# DecoderCircuit_M2.net
KiCad netlist of a schematic drawn in Altium Designer
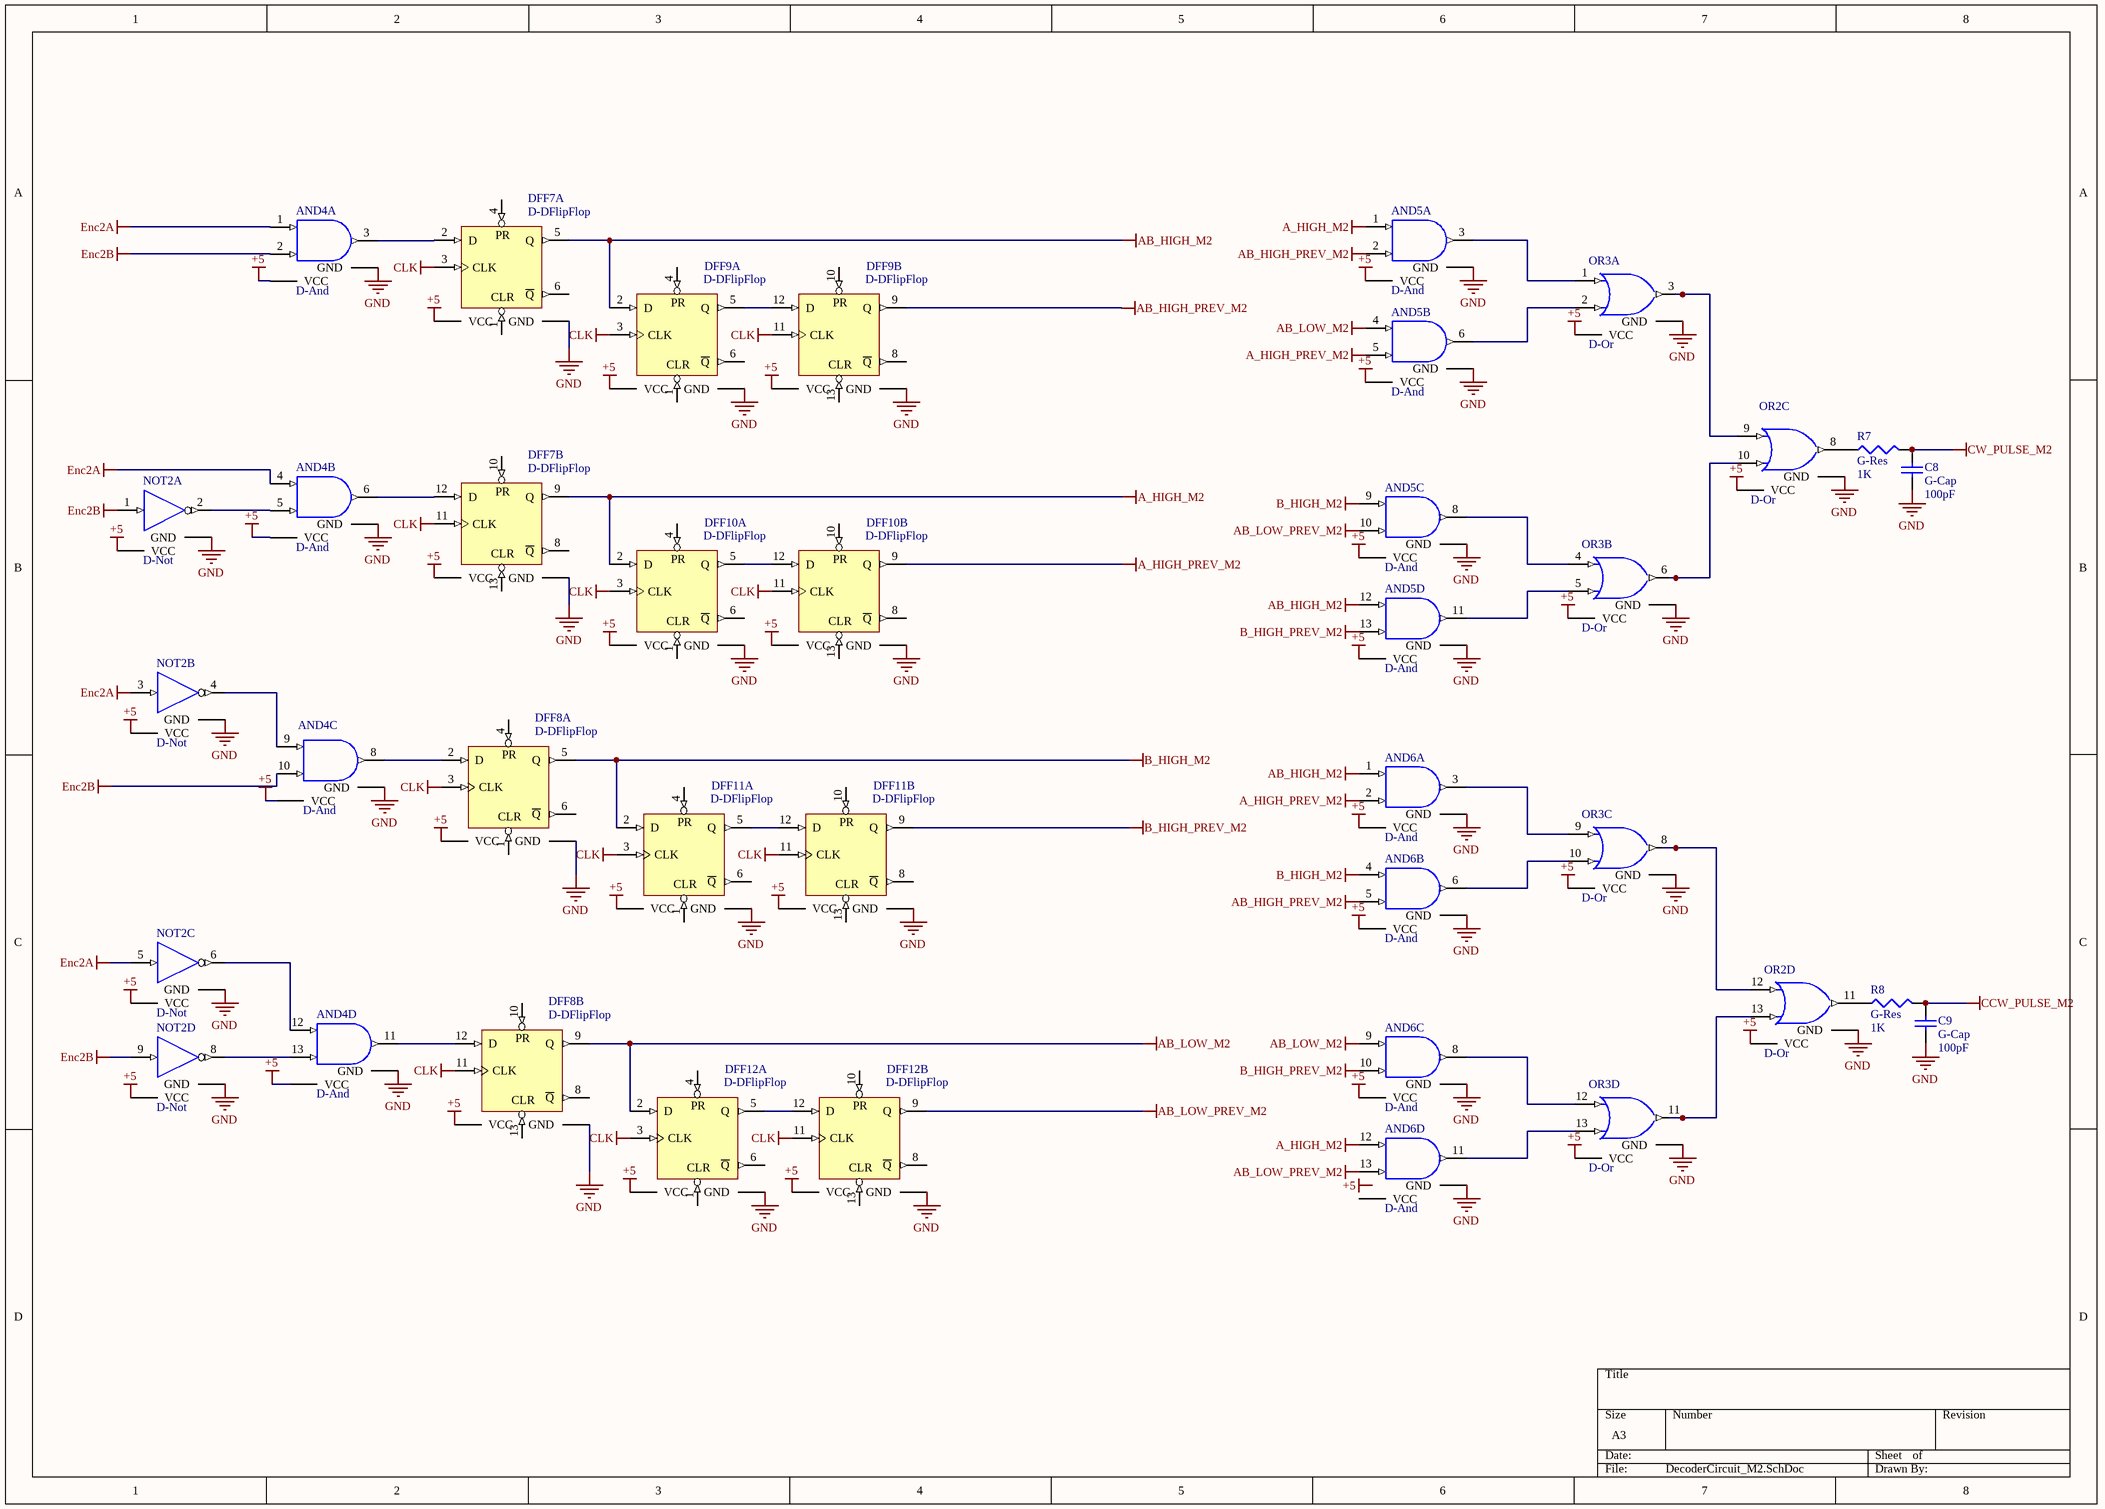
[diagram p0: DecoderCircuit_M2.SchDoc]

(export (version "E")
  (design (tool "Eeschema 10.0.6"))
  (components
    (comp (ref "AND4")
      (value "D-And")
      (footprint "DIP14_LGE1.0")
      (description "Quad 2-input AND gate")
      (fields (field (name "PUBLISHER") "Altium Limited"))
      (libsource (lib "PartsDatabaseV16.1") (part "D-And"))
    )
    (comp (ref "AND5")
      (value "D-And")
      (footprint "DIP14_LGE1.0")
      (description "Quad 2-input AND gate")
      (fields (field (name "PUBLISHER") "Altium Limited"))
      (libsource (lib "PartsDatabaseV16.1") (part "D-And"))
    )
    (comp (ref "AND6")
      (value "D-And")
      (footprint "DIP14_LGE1.0")
      (description "Quad 2-input AND gate")
      (fields (field (name "PUBLISHER") "Altium Limited"))
      (libsource (lib "PartsDatabaseV16.1") (part "D-And"))
    )
    (comp (ref "C8")
      (value "G-Cap")
      (footprint "Cap2.54mm_LGE1.0")
      (description "Capacitor (specify value)")
      (fields (field (name "ALTIUM_VALUE") "100pF") (field (name "PUBLISHER") "Altium Limited"))
      (libsource (lib "PartsDatabaseV16.1") (part "G-Cap"))
    )
    (comp (ref "C9")
      (value "G-Cap")
      (footprint "Cap2.54mm_LGE1.0")
      (description "Capacitor (specify value)")
      (fields (field (name "ALTIUM_VALUE") "100pF") (field (name "PUBLISHER") "Altium Limited"))
      (libsource (lib "PartsDatabaseV16.1") (part "G-Cap"))
    )
    (comp (ref "DFF7")
      (value "D-DFlipFlop")
      (footprint "DIP14_LGE1.0")
      (description "Dual D flip-flop")
      (fields (field (name "PUBLISHER") "Altium Limited"))
      (libsource (lib "PartsDatabaseV16.1") (part "D-DFlipFlop"))
    )
    (comp (ref "DFF8")
      (value "D-DFlipFlop")
      (footprint "DIP14_LGE1.0")
      (description "Dual D flip-flop")
      (fields (field (name "PUBLISHER") "Altium Limited"))
      (libsource (lib "PartsDatabaseV16.1") (part "D-DFlipFlop"))
    )
    (comp (ref "DFF9")
      (value "D-DFlipFlop")
      (footprint "DIP14_LGE1.0")
      (description "Dual D flip-flop")
      (fields (field (name "PUBLISHER") "Altium Limited"))
      (libsource (lib "PartsDatabaseV16.1") (part "D-DFlipFlop"))
    )
    (comp (ref "DFF10")
      (value "D-DFlipFlop")
      (footprint "DIP14_LGE1.0")
      (description "Dual D flip-flop")
      (fields (field (name "PUBLISHER") "Altium Limited"))
      (libsource (lib "PartsDatabaseV16.1") (part "D-DFlipFlop"))
    )
    (comp (ref "DFF11")
      (value "D-DFlipFlop")
      (footprint "DIP14_LGE1.0")
      (description "Dual D flip-flop")
      (fields (field (name "PUBLISHER") "Altium Limited"))
      (libsource (lib "PartsDatabaseV16.1") (part "D-DFlipFlop"))
    )
    (comp (ref "DFF12")
      (value "D-DFlipFlop")
      (footprint "DIP14_LGE1.0")
      (description "Dual D flip-flop")
      (fields (field (name "PUBLISHER") "Altium Limited"))
      (libsource (lib "PartsDatabaseV16.1") (part "D-DFlipFlop"))
    )
    (comp (ref "NOT2")
      (value "D-Not")
      (footprint "DIP14_LGE1.0")
      (description "Hex NOT gate (inverter)")
      (fields (field (name "PUBLISHER") "Altium Limited"))
      (libsource (lib "PartsDatabaseV16.1") (part "D-Not"))
    )
    (comp (ref "OR2")
      (value "D-Or")
      (footprint "DIP14_LGE1.0")
      (description "Quad 2-input OR gate")
      (fields (field (name "PUBLISHER") "Altium Limited"))
      (libsource (lib "PartsDatabaseV16.1") (part "D-Or"))
    )
    (comp (ref "OR3")
      (value "D-Or")
      (footprint "DIP14_LGE1.0")
      (description "Quad 2-input OR gate")
      (fields (field (name "PUBLISHER") "Altium Limited"))
      (libsource (lib "PartsDatabaseV16.1") (part "D-Or"))
    )
    (comp (ref "R7")
      (value "G-Res")
      (footprint "Res10mm_LGE1.0")
      (description "Resistor (specify value)")
      (fields (field (name "ALTIUM_VALUE") "1K") (field (name "PUBLISHER") "Altium Limited"))
      (libsource (lib "PartsDatabaseV16.1") (part "G-Res"))
    )
    (comp (ref "R8")
      (value "G-Res")
      (footprint "Res10mm_LGE1.0")
      (description "Resistor (specify value)")
      (fields (field (name "ALTIUM_VALUE") "1K") (field (name "PUBLISHER") "Altium Limited"))
      (libsource (lib "PartsDatabaseV16.1") (part "G-Res"))
    )
  )
  (nets
    (net (code "1") (name "+5") (class "Default")
      (node (ref "AND4") (pin "14") (pinfunction "VCC_14") (pintype "power_in"))
      (node (ref "AND5") (pin "14") (pinfunction "VCC_14") (pintype "power_in"))
      (node (ref "AND6") (pin "14") (pinfunction "VCC_14") (pintype "power_in"))
      (node (ref "DFF10") (pin "14") (pinfunction "VCC_14") (pintype "power_in"))
      (node (ref "DFF11") (pin "14") (pinfunction "VCC_14") (pintype "power_in"))
      (node (ref "DFF12") (pin "14") (pinfunction "VCC_14") (pintype "power_in"))
      (node (ref "DFF7") (pin "14") (pinfunction "VCC_14") (pintype "power_in"))
      (node (ref "DFF8") (pin "14") (pinfunction "VCC_14") (pintype "power_in"))
      (node (ref "DFF9") (pin "14") (pinfunction "VCC_14") (pintype "power_in"))
      (node (ref "NOT2") (pin "14") (pinfunction "VCC_14") (pintype "power_in"))
      (node (ref "OR2") (pin "14") (pinfunction "VCC_14") (pintype "power_in"))
      (node (ref "OR3") (pin "14") (pinfunction "VCC_14") (pintype "power_in"))
    )
    (net (code "2") (name "AB_HIGH_M2") (class "Default")
      (node (ref "AND5") (pin "12") (pinfunction "A_12") (pintype "input"))
      (node (ref "AND6") (pin "1") (pinfunction "A_1") (pintype "input"))
      (node (ref "DFF7") (pin "5") (pinfunction "Q_5") (pintype "output"))
      (node (ref "DFF9") (pin "2") (pinfunction "D_2") (pintype "input"))
    )
    (net (code "3") (name "AB_HIGH_PREV_M2") (class "Default")
      (node (ref "AND5") (pin "2") (pinfunction "B_2") (pintype "input"))
      (node (ref "AND6") (pin "5") (pinfunction "B_5") (pintype "input"))
      (node (ref "DFF9") (pin "9") (pinfunction "Q_9") (pintype "output"))
    )
    (net (code "4") (name "AB_LOW_M2") (class "Default")
      (node (ref "AND5") (pin "4") (pinfunction "A_4") (pintype "input"))
      (node (ref "AND6") (pin "9") (pinfunction "A_9") (pintype "input"))
      (node (ref "DFF12") (pin "2") (pinfunction "D_2") (pintype "input"))
      (node (ref "DFF8") (pin "9") (pinfunction "Q_9") (pintype "output"))
    )
    (net (code "5") (name "AB_LOW_PREV_M2") (class "Default")
      (node (ref "AND5") (pin "10") (pinfunction "B_10") (pintype "input"))
      (node (ref "AND6") (pin "13") (pinfunction "B_13") (pintype "input"))
      (node (ref "DFF12") (pin "9") (pinfunction "Q_9") (pintype "output"))
    )
    (net (code "6") (name "A_HIGH_M2") (class "Default")
      (node (ref "AND5") (pin "1") (pinfunction "A_1") (pintype "input"))
      (node (ref "AND6") (pin "12") (pinfunction "A_12") (pintype "input"))
      (node (ref "DFF10") (pin "2") (pinfunction "D_2") (pintype "input"))
      (node (ref "DFF7") (pin "9") (pinfunction "Q_9") (pintype "output"))
    )
    (net (code "7") (name "A_HIGH_PREV_M2") (class "Default")
      (node (ref "AND5") (pin "5") (pinfunction "B_5") (pintype "input"))
      (node (ref "AND6") (pin "2") (pinfunction "B_2") (pintype "input"))
      (node (ref "DFF10") (pin "9") (pinfunction "Q_9") (pintype "output"))
    )
    (net (code "8") (name "B_HIGH_M2") (class "Default")
      (node (ref "AND5") (pin "9") (pinfunction "A_9") (pintype "input"))
      (node (ref "AND6") (pin "4") (pinfunction "A_4") (pintype "input"))
      (node (ref "DFF11") (pin "2") (pinfunction "D_2") (pintype "input"))
      (node (ref "DFF8") (pin "5") (pinfunction "Q_5") (pintype "output"))
    )
    (net (code "9") (name "B_HIGH_PREV_M2") (class "Default")
      (node (ref "AND5") (pin "13") (pinfunction "B_13") (pintype "input"))
      (node (ref "AND6") (pin "10") (pinfunction "B_10") (pintype "input"))
      (node (ref "DFF11") (pin "9") (pinfunction "Q_9") (pintype "output"))
    )
    (net (code "10") (name "CCW_PULSE_M2") (class "Default")
      (node (ref "C9") (pin "1") (pinfunction "1_1") (pintype "passive"))
      (node (ref "R8") (pin "2") (pinfunction "2_2") (pintype "passive"))
    )
    (net (code "11") (name "CLK") (class "Default")
      (node (ref "DFF10") (pin "11") (pinfunction "CLK_11") (pintype "input"))
      (node (ref "DFF10") (pin "3") (pinfunction "CLK_3") (pintype "input"))
      (node (ref "DFF11") (pin "11") (pinfunction "CLK_11") (pintype "input"))
      (node (ref "DFF11") (pin "3") (pinfunction "CLK_3") (pintype "input"))
      (node (ref "DFF12") (pin "11") (pinfunction "CLK_11") (pintype "input"))
      (node (ref "DFF12") (pin "3") (pinfunction "CLK_3") (pintype "input"))
      (node (ref "DFF7") (pin "11") (pinfunction "CLK_11") (pintype "input"))
      (node (ref "DFF7") (pin "3") (pinfunction "CLK_3") (pintype "input"))
      (node (ref "DFF8") (pin "11") (pinfunction "CLK_11") (pintype "input"))
      (node (ref "DFF8") (pin "3") (pinfunction "CLK_3") (pintype "input"))
      (node (ref "DFF9") (pin "11") (pinfunction "CLK_11") (pintype "input"))
      (node (ref "DFF9") (pin "3") (pinfunction "CLK_3") (pintype "input"))
    )
    (net (code "12") (name "CW_PULSE_M2") (class "Default")
      (node (ref "C8") (pin "1") (pinfunction "1_1") (pintype "passive"))
      (node (ref "R7") (pin "2") (pinfunction "2_2") (pintype "passive"))
    )
    (net (code "13") (name "Enc2A") (class "Default")
      (node (ref "AND4") (pin "1") (pinfunction "A_1") (pintype "input"))
      (node (ref "AND4") (pin "4") (pinfunction "A_4") (pintype "input"))
      (node (ref "NOT2") (pin "3") (pinfunction "A_3") (pintype "input"))
      (node (ref "NOT2") (pin "5") (pinfunction "A_5") (pintype "input"))
    )
    (net (code "14") (name "Enc2B") (class "Default")
      (node (ref "AND4") (pin "10") (pinfunction "B_10") (pintype "input"))
      (node (ref "AND4") (pin "2") (pinfunction "B_2") (pintype "input"))
      (node (ref "NOT2") (pin "1") (pinfunction "A_1") (pintype "input"))
      (node (ref "NOT2") (pin "9") (pinfunction "A_9") (pintype "input"))
    )
    (net (code "15") (name "GND") (class "Default")
      (node (ref "AND4") (pin "7") (pinfunction "GND_7") (pintype "power_in"))
      (node (ref "AND5") (pin "7") (pinfunction "GND_7") (pintype "power_in"))
      (node (ref "AND6") (pin "7") (pinfunction "GND_7") (pintype "power_in"))
      (node (ref "C8") (pin "2") (pinfunction "2_2") (pintype "passive"))
      (node (ref "C9") (pin "2") (pinfunction "2_2") (pintype "passive"))
      (node (ref "DFF10") (pin "7") (pinfunction "GND_7") (pintype "power_in"))
      (node (ref "DFF11") (pin "7") (pinfunction "GND_7") (pintype "power_in"))
      (node (ref "DFF12") (pin "7") (pinfunction "GND_7") (pintype "power_in"))
      (node (ref "DFF7") (pin "7") (pinfunction "GND_7") (pintype "power_in"))
      (node (ref "DFF8") (pin "7") (pinfunction "GND_7") (pintype "power_in"))
      (node (ref "DFF9") (pin "7") (pinfunction "GND_7") (pintype "power_in"))
      (node (ref "NOT2") (pin "7") (pinfunction "GND_7") (pintype "power_in"))
      (node (ref "OR2") (pin "7") (pinfunction "GND_7") (pintype "power_in"))
      (node (ref "OR3") (pin "7") (pinfunction "GND_7") (pintype "power_in"))
    )
    (net (code "16") (name "Net-(AND4A-Y)") (class "Default")
      (node (ref "AND4") (pin "3") (pinfunction "Y_3") (pintype "output"))
      (node (ref "DFF7") (pin "2") (pinfunction "D_2") (pintype "input"))
    )
    (net (code "17") (name "Net-(AND4B-B)") (class "Default")
      (node (ref "AND4") (pin "5") (pinfunction "B_5") (pintype "input"))
      (node (ref "NOT2") (pin "2") (pinfunction "Y_2") (pintype "output"))
    )
    (net (code "18") (name "Net-(AND4B-Y)") (class "Default")
      (node (ref "AND4") (pin "6") (pinfunction "Y_6") (pintype "output"))
      (node (ref "DFF7") (pin "12") (pinfunction "D_12") (pintype "input"))
    )
    (net (code "19") (name "Net-(AND4C-A)") (class "Default")
      (node (ref "AND4") (pin "9") (pinfunction "A_9") (pintype "input"))
      (node (ref "NOT2") (pin "4") (pinfunction "Y_4") (pintype "output"))
    )
    (net (code "20") (name "Net-(AND4C-Y)") (class "Default")
      (node (ref "AND4") (pin "8") (pinfunction "Y_8") (pintype "output"))
      (node (ref "DFF8") (pin "2") (pinfunction "D_2") (pintype "input"))
    )
    (net (code "21") (name "Net-(AND4D-A)") (class "Default")
      (node (ref "AND4") (pin "12") (pinfunction "A_12") (pintype "input"))
      (node (ref "NOT2") (pin "6") (pinfunction "Y_6") (pintype "output"))
    )
    (net (code "22") (name "Net-(AND4D-B)") (class "Default")
      (node (ref "AND4") (pin "13") (pinfunction "B_13") (pintype "input"))
      (node (ref "NOT2") (pin "8") (pinfunction "Y_8") (pintype "output"))
    )
    (net (code "23") (name "Net-(AND4D-Y)") (class "Default")
      (node (ref "AND4") (pin "11") (pinfunction "Y_11") (pintype "output"))
      (node (ref "DFF8") (pin "12") (pinfunction "D_12") (pintype "input"))
    )
    (net (code "24") (name "Net-(AND5A-Y)") (class "Default")
      (node (ref "AND5") (pin "3") (pinfunction "Y_3") (pintype "output"))
      (node (ref "OR3") (pin "1") (pinfunction "A_1") (pintype "input"))
    )
    (net (code "25") (name "Net-(AND5B-Y)") (class "Default")
      (node (ref "AND5") (pin "6") (pinfunction "Y_6") (pintype "output"))
      (node (ref "OR3") (pin "2") (pinfunction "B_2") (pintype "input"))
    )
    (net (code "26") (name "Net-(AND5C-Y)") (class "Default")
      (node (ref "AND5") (pin "8") (pinfunction "Y_8") (pintype "output"))
      (node (ref "OR3") (pin "4") (pinfunction "A_4") (pintype "input"))
    )
    (net (code "27") (name "Net-(AND5D-Y)") (class "Default")
      (node (ref "AND5") (pin "11") (pinfunction "Y_11") (pintype "output"))
      (node (ref "OR3") (pin "5") (pinfunction "B_5") (pintype "input"))
    )
    (net (code "28") (name "Net-(AND6A-Y)") (class "Default")
      (node (ref "AND6") (pin "3") (pinfunction "Y_3") (pintype "output"))
      (node (ref "OR3") (pin "9") (pinfunction "A_9") (pintype "input"))
    )
    (net (code "29") (name "Net-(AND6B-Y)") (class "Default")
      (node (ref "AND6") (pin "6") (pinfunction "Y_6") (pintype "output"))
      (node (ref "OR3") (pin "10") (pinfunction "B_10") (pintype "input"))
    )
    (net (code "30") (name "Net-(AND6C-Y)") (class "Default")
      (node (ref "AND6") (pin "8") (pinfunction "Y_8") (pintype "output"))
      (node (ref "OR3") (pin "12") (pinfunction "A_12") (pintype "input"))
    )
    (net (code "31") (name "Net-(AND6D-Y)") (class "Default")
      (node (ref "AND6") (pin "11") (pinfunction "Y_11") (pintype "output"))
      (node (ref "OR3") (pin "13") (pinfunction "B_13") (pintype "input"))
    )
    (net (code "32") (name "Net-(DFF9A-Q)") (class "Default")
      (node (ref "DFF9") (pin "12") (pinfunction "D_12") (pintype "input"))
      (node (ref "DFF9") (pin "5") (pinfunction "Q_5") (pintype "output"))
    )
    (net (code "33") (name "Net-(DFF10A-Q)") (class "Default")
      (node (ref "DFF10") (pin "12") (pinfunction "D_12") (pintype "input"))
      (node (ref "DFF10") (pin "5") (pinfunction "Q_5") (pintype "output"))
    )
    (net (code "34") (name "Net-(DFF11A-Q)") (class "Default")
      (node (ref "DFF11") (pin "12") (pinfunction "D_12") (pintype "input"))
      (node (ref "DFF11") (pin "5") (pinfunction "Q_5") (pintype "output"))
    )
    (net (code "35") (name "Net-(DFF12A-Q)") (class "Default")
      (node (ref "DFF12") (pin "12") (pinfunction "D_12") (pintype "input"))
      (node (ref "DFF12") (pin "5") (pinfunction "Q_5") (pintype "output"))
    )
    (net (code "36") (name "Net-(OR2C-A)") (class "Default")
      (node (ref "OR2") (pin "9") (pinfunction "A_9") (pintype "input"))
      (node (ref "OR3") (pin "3") (pinfunction "Y_3") (pintype "output"))
    )
    (net (code "37") (name "Net-(OR2C-B)") (class "Default")
      (node (ref "OR2") (pin "10") (pinfunction "B_10") (pintype "input"))
      (node (ref "OR3") (pin "6") (pinfunction "Y_6") (pintype "output"))
    )
    (net (code "38") (name "Net-(OR2C-Y)") (class "Default")
      (node (ref "OR2") (pin "8") (pinfunction "Y_8") (pintype "output"))
      (node (ref "R7") (pin "1") (pinfunction "1_1") (pintype "passive"))
    )
    (net (code "39") (name "Net-(OR2D-A)") (class "Default")
      (node (ref "OR2") (pin "12") (pinfunction "A_12") (pintype "input"))
      (node (ref "OR3") (pin "8") (pinfunction "Y_8") (pintype "output"))
    )
    (net (code "40") (name "Net-(OR2D-B)") (class "Default")
      (node (ref "OR2") (pin "13") (pinfunction "B_13") (pintype "input"))
      (node (ref "OR3") (pin "11") (pinfunction "Y_11") (pintype "output"))
    )
    (net (code "41") (name "Net-(OR2D-Y)") (class "Default")
      (node (ref "OR2") (pin "11") (pinfunction "Y_11") (pintype "output"))
      (node (ref "R8") (pin "1") (pinfunction "1_1") (pintype "passive"))
    )
    (net (code "42") (name "unconnected-(AND6D-VCC-Pad14)") (class "Default")
      (node (ref "AND6") (pin "14") (pinfunction "VCC_14") (pintype "power_in"))
    )
    (net (code "43") (name "unconnected-(DFF7A-CLR-Pad1)") (class "Default")
      (node (ref "DFF7") (pin "1") (pinfunction "CLR_1") (pintype "input"))
    )
    (net (code "44") (name "unconnected-(DFF7A-PR-Pad4)") (class "Default")
      (node (ref "DFF7") (pin "4") (pinfunction "PR_4") (pintype "input"))
    )
    (net (code "45") (name "unconnected-(DFF7A-~{Q}-Pad6)") (class "Default")
      (node (ref "DFF7") (pin "6") (pinfunction "~{Q}_6") (pintype "output"))
    )
    (net (code "46") (name "unconnected-(DFF7B-CLR-Pad13)") (class "Default")
      (node (ref "DFF7") (pin "13") (pinfunction "CLR_13") (pintype "input"))
    )
    (net (code "47") (name "unconnected-(DFF7B-PR-Pad10)") (class "Default")
      (node (ref "DFF7") (pin "10") (pinfunction "PR_10") (pintype "input"))
    )
    (net (code "48") (name "unconnected-(DFF7B-~{Q}-Pad8)") (class "Default")
      (node (ref "DFF7") (pin "8") (pinfunction "~{Q}_8") (pintype "output"))
    )
    (net (code "49") (name "unconnected-(DFF8A-CLR-Pad1)") (class "Default")
      (node (ref "DFF8") (pin "1") (pinfunction "CLR_1") (pintype "input"))
    )
    (net (code "50") (name "unconnected-(DFF8A-PR-Pad4)") (class "Default")
      (node (ref "DFF8") (pin "4") (pinfunction "PR_4") (pintype "input"))
    )
    (net (code "51") (name "unconnected-(DFF8A-~{Q}-Pad6)") (class "Default")
      (node (ref "DFF8") (pin "6") (pinfunction "~{Q}_6") (pintype "output"))
    )
    (net (code "52") (name "unconnected-(DFF8B-CLR-Pad13)") (class "Default")
      (node (ref "DFF8") (pin "13") (pinfunction "CLR_13") (pintype "input"))
    )
    (net (code "53") (name "unconnected-(DFF8B-PR-Pad10)") (class "Default")
      (node (ref "DFF8") (pin "10") (pinfunction "PR_10") (pintype "input"))
    )
    (net (code "54") (name "unconnected-(DFF8B-~{Q}-Pad8)") (class "Default")
      (node (ref "DFF8") (pin "8") (pinfunction "~{Q}_8") (pintype "output"))
    )
    (net (code "55") (name "unconnected-(DFF9A-CLR-Pad1)") (class "Default")
      (node (ref "DFF9") (pin "1") (pinfunction "CLR_1") (pintype "input"))
    )
    (net (code "56") (name "unconnected-(DFF9A-PR-Pad4)") (class "Default")
      (node (ref "DFF9") (pin "4") (pinfunction "PR_4") (pintype "input"))
    )
    (net (code "57") (name "unconnected-(DFF9A-~{Q}-Pad6)") (class "Default")
      (node (ref "DFF9") (pin "6") (pinfunction "~{Q}_6") (pintype "output"))
    )
    (net (code "58") (name "unconnected-(DFF9B-CLR-Pad13)") (class "Default")
      (node (ref "DFF9") (pin "13") (pinfunction "CLR_13") (pintype "input"))
    )
    (net (code "59") (name "unconnected-(DFF9B-PR-Pad10)") (class "Default")
      (node (ref "DFF9") (pin "10") (pinfunction "PR_10") (pintype "input"))
    )
    (net (code "60") (name "unconnected-(DFF9B-~{Q}-Pad8)") (class "Default")
      (node (ref "DFF9") (pin "8") (pinfunction "~{Q}_8") (pintype "output"))
    )
    (net (code "61") (name "unconnected-(DFF10A-CLR-Pad1)") (class "Default")
      (node (ref "DFF10") (pin "1") (pinfunction "CLR_1") (pintype "input"))
    )
    (net (code "62") (name "unconnected-(DFF10A-PR-Pad4)") (class "Default")
      (node (ref "DFF10") (pin "4") (pinfunction "PR_4") (pintype "input"))
    )
    (net (code "63") (name "unconnected-(DFF10A-~{Q}-Pad6)") (class "Default")
      (node (ref "DFF10") (pin "6") (pinfunction "~{Q}_6") (pintype "output"))
    )
    (net (code "64") (name "unconnected-(DFF10B-CLR-Pad13)") (class "Default")
      (node (ref "DFF10") (pin "13") (pinfunction "CLR_13") (pintype "input"))
    )
    (net (code "65") (name "unconnected-(DFF10B-PR-Pad10)") (class "Default")
      (node (ref "DFF10") (pin "10") (pinfunction "PR_10") (pintype "input"))
    )
    (net (code "66") (name "unconnected-(DFF10B-~{Q}-Pad8)") (class "Default")
      (node (ref "DFF10") (pin "8") (pinfunction "~{Q}_8") (pintype "output"))
    )
    (net (code "67") (name "unconnected-(DFF11A-CLR-Pad1)") (class "Default")
      (node (ref "DFF11") (pin "1") (pinfunction "CLR_1") (pintype "input"))
    )
    (net (code "68") (name "unconnected-(DFF11A-PR-Pad4)") (class "Default")
      (node (ref "DFF11") (pin "4") (pinfunction "PR_4") (pintype "input"))
    )
    (net (code "69") (name "unconnected-(DFF11A-~{Q}-Pad6)") (class "Default")
      (node (ref "DFF11") (pin "6") (pinfunction "~{Q}_6") (pintype "output"))
    )
    (net (code "70") (name "unconnected-(DFF11B-CLR-Pad13)") (class "Default")
      (node (ref "DFF11") (pin "13") (pinfunction "CLR_13") (pintype "input"))
    )
    (net (code "71") (name "unconnected-(DFF11B-PR-Pad10)") (class "Default")
      (node (ref "DFF11") (pin "10") (pinfunction "PR_10") (pintype "input"))
    )
    (net (code "72") (name "unconnected-(DFF11B-~{Q}-Pad8)") (class "Default")
      (node (ref "DFF11") (pin "8") (pinfunction "~{Q}_8") (pintype "output"))
    )
    (net (code "73") (name "unconnected-(DFF12A-CLR-Pad1)") (class "Default")
      (node (ref "DFF12") (pin "1") (pinfunction "CLR_1") (pintype "input"))
    )
    (net (code "74") (name "unconnected-(DFF12A-PR-Pad4)") (class "Default")
      (node (ref "DFF12") (pin "4") (pinfunction "PR_4") (pintype "input"))
    )
    (net (code "75") (name "unconnected-(DFF12A-~{Q}-Pad6)") (class "Default")
      (node (ref "DFF12") (pin "6") (pinfunction "~{Q}_6") (pintype "output"))
    )
    (net (code "76") (name "unconnected-(DFF12B-CLR-Pad13)") (class "Default")
      (node (ref "DFF12") (pin "13") (pinfunction "CLR_13") (pintype "input"))
    )
    (net (code "77") (name "unconnected-(DFF12B-PR-Pad10)") (class "Default")
      (node (ref "DFF12") (pin "10") (pinfunction "PR_10") (pintype "input"))
    )
    (net (code "78") (name "unconnected-(DFF12B-~{Q}-Pad8)") (class "Default")
      (node (ref "DFF12") (pin "8") (pinfunction "~{Q}_8") (pintype "output"))
    )
  )
)
